# G4y_SuperCap.net
KiCad netlist of a schematic drawn in Altium Designer
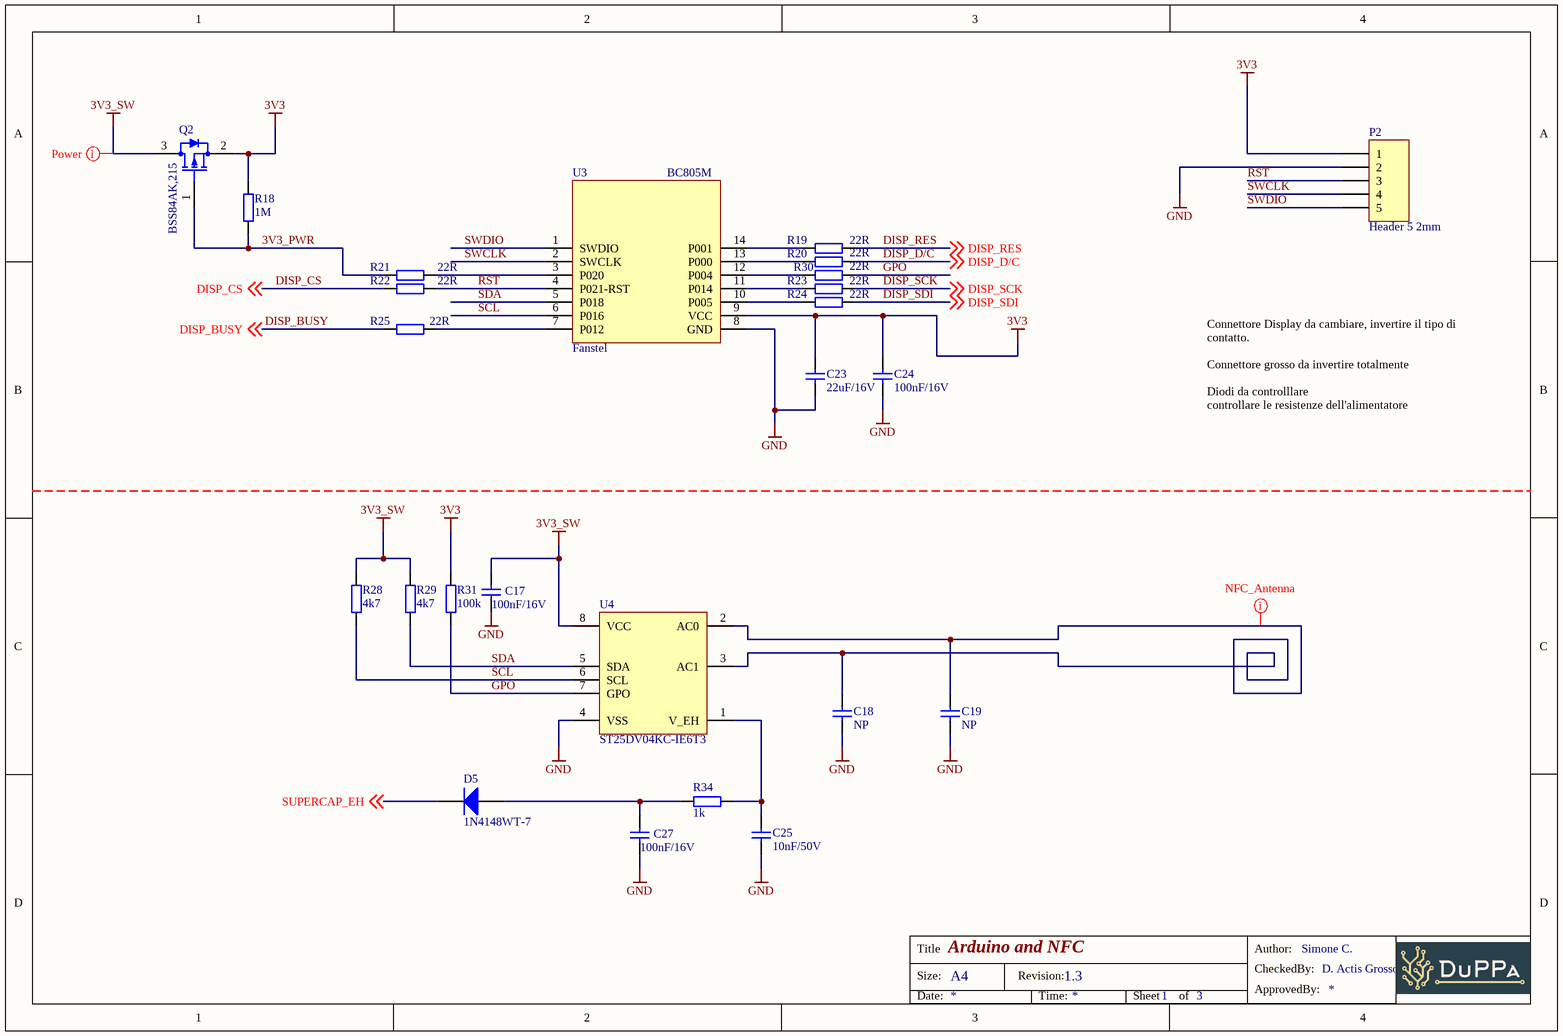
[diagram p0: G4y_SuperCap.SchDoc]

(export (version "E")
  (design (tool "Eeschema 10.0.6"))
  (components
    (comp (ref "C17")
      (value "100nF/16V")
      (footprint "C0402")
      (description "16V 100nF X7R ±10% 0402 Multilayer Ceramic Capacitors MLCC - SMD/SMT ROHS")
      (fields
        (field (name "PARTNUMBER") "CL05B104KO5NNNC")
        (field (name "MANUFACTURER") "Samsung Electro-Mechanics")
      )
      (libsource (lib "DuPPa_Lib") (part "Cap_0402_100n/16V"))
    )
    (comp (ref "C18")
      (value "NP")
      (footprint "C0402")
      (fields (field (name "Comment") "Cap_0402_NP"))
      (libsource (lib "DuPPa_Lib") (part "Cap_0402_NP"))
    )
    (comp (ref "C19")
      (value "NP")
      (footprint "C0402")
      (fields (field (name "Comment") "Cap_0402_NP"))
      (libsource (lib "DuPPa_Lib") (part "Cap_0402_NP"))
    )
    (comp (ref "C23")
      (value "22uF/16V")
      (footprint "C0805")
      (description "22uF ±20% 16V Ceramic Capacitor X5R 0805")
      (fields
        (field (name "PARTNUMBER") "CL21A226MOQNNNE")
        (field (name "MANUFACTURER") "Samsung Electro-Mechanics")
      )
      (libsource (lib "DuPPa_Lib") (part "Cap_0805_22uF/16V"))
    )
    (comp (ref "C24")
      (value "100nF/16V")
      (footprint "C0402")
      (description "16V 100nF X7R ±10% 0402 Multilayer Ceramic Capacitors MLCC - SMD/SMT ROHS")
      (fields
        (field (name "PARTNUMBER") "CL05B104KO5NNNC")
        (field (name "MANUFACTURER") "Samsung Electro-Mechanics")
      )
      (libsource (lib "DuPPa_Lib") (part "Cap_0402_100n/16V"))
    )
    (comp (ref "C25")
      (value "10nF/50V")
      (footprint "C0402")
      (description "10nF ±10% 50V Ceramic Capacitor X7R 0402")
      (fields
        (field (name "PARTNUMBER") "CL05B103KB5NNNC")
        (field (name "MANUFACTURER") "Samsung Electro-Mechanics")
      )
      (libsource (lib "DuPPa_Lib") (part "Cap_0402_10nF/50V"))
    )
    (comp (ref "C27")
      (value "100nF/16V")
      (footprint "C0402")
      (description "16V 100nF X7R ±10% 0402 Multilayer Ceramic Capacitors MLCC - SMD/SMT ROHS")
      (fields
        (field (name "PARTNUMBER") "CL05B104KO5NNNC")
        (field (name "MANUFACTURER") "Samsung Electro-Mechanics")
      )
      (libsource (lib "DuPPa_Lib") (part "Cap_0402_100n/16V"))
    )
    (comp (ref "D5")
      (value "Diode_1N4148WT")
      (footprint "SODFL160X65-2N")
      (description "Diode Independent 80V 125mA Surface Mount SOD-523")
      (fields (field (name "PARTNUMBER") "1N4148WT-7") (field (name "MANUFACTURER") "Diodes"))
      (libsource (lib "DuPPa_Lib") (part "Diode_1N4148WT"))
    )
    (comp (ref "P2")
      (value "Header 5 2mm")
      (footprint "HDR1X5_2mm")
      (description "Header, 5-Pin")
      (libsource (lib "DuPPa_Lib") (part "Header 5 2mm"))
    )
    (comp (ref "Q2")
      (value "BSS84AKBSS84AK,215")
      (footprint "SOT-23-3")
      (description "P-Channel 50V 180mA 420mW Surface Mount SOT-23")
      (fields (field (name "MANUFACTURER") "Nexperia") (field (name "PARTNUMBER") "BSS84AK,215"))
      (libsource (lib "DuPPa_Lib") (part "BSS84AKBSS84AK,215"))
    )
    (comp (ref "R18")
      (value "1M")
      (footprint "R0402")
      (description "1MΩ ±1% 62.5mW 0402 Thick Film Resistor")
      (fields (field (name "PARTNUMBER") "0402WGF1004TCE") (field (name "MANUFACTURER") "UNI-ROYAL"))
      (libsource (lib "DuPPa_Lib") (part "R_R0402_1M"))
    )
    (comp (ref "R19")
      (value "22R")
      (footprint "R0402")
      (description "22Ω ±1% 62.5mW 0402 Thick Film Resistor")
      (fields (field (name "PARTNUMBER") "0402WGF220JTCE") (field (name "MANUFACTURER") "UNI-ROYAL"))
      (libsource (lib "DuPPa_Lib") (part "R_R0402_22R"))
    )
    (comp (ref "R20")
      (value "22R")
      (footprint "R0402")
      (description "22Ω ±1% 62.5mW 0402 Thick Film Resistor")
      (fields (field (name "PARTNUMBER") "0402WGF220JTCE") (field (name "MANUFACTURER") "UNI-ROYAL"))
      (libsource (lib "DuPPa_Lib") (part "R_R0402_22R"))
    )
    (comp (ref "R21")
      (value "22R")
      (footprint "R0402")
      (description "22Ω ±1% 62.5mW 0402 Thick Film Resistor")
      (fields (field (name "PARTNUMBER") "0402WGF220JTCE") (field (name "MANUFACTURER") "UNI-ROYAL"))
      (libsource (lib "DuPPa_Lib") (part "R_R0402_22R"))
    )
    (comp (ref "R22")
      (value "22R")
      (footprint "R0402")
      (description "22Ω ±1% 62.5mW 0402 Thick Film Resistor")
      (fields (field (name "PARTNUMBER") "0402WGF220JTCE") (field (name "MANUFACTURER") "UNI-ROYAL"))
      (libsource (lib "DuPPa_Lib") (part "R_R0402_22R"))
    )
    (comp (ref "R23")
      (value "22R")
      (footprint "R0402")
      (description "22Ω ±1% 62.5mW 0402 Thick Film Resistor")
      (fields (field (name "PARTNUMBER") "0402WGF220JTCE") (field (name "MANUFACTURER") "UNI-ROYAL"))
      (libsource (lib "DuPPa_Lib") (part "R_R0402_22R"))
    )
    (comp (ref "R24")
      (value "22R")
      (footprint "R0402")
      (description "22Ω ±1% 62.5mW 0402 Thick Film Resistor")
      (fields (field (name "PARTNUMBER") "0402WGF220JTCE") (field (name "MANUFACTURER") "UNI-ROYAL"))
      (libsource (lib "DuPPa_Lib") (part "R_R0402_22R"))
    )
    (comp (ref "R25")
      (value "22R")
      (footprint "R0402")
      (description "22Ω ±1% 62.5mW 0402 Thick Film Resistor")
      (fields (field (name "PARTNUMBER") "0402WGF220JTCE") (field (name "MANUFACTURER") "UNI-ROYAL"))
      (libsource (lib "DuPPa_Lib") (part "R_R0402_22R"))
    )
    (comp (ref "R28")
      (value "4k7")
      (footprint "R0402")
      (description "0402, 1% ,63mW")
      (fields (field (name "PARTNUMBER") "0402WGF4701TCE") (field (name "Comment") "R_R0402_4k7"))
      (libsource (lib "DuPPa_Lib") (part "R_R0402_4k7"))
    )
    (comp (ref "R29")
      (value "4k7")
      (footprint "R0402")
      (description "0402, 1% ,63mW")
      (fields (field (name "PARTNUMBER") "0402WGF4701TCE") (field (name "Comment") "R_R0402_4k7"))
      (libsource (lib "DuPPa_Lib") (part "R_R0402_4k7"))
    )
    (comp (ref "R30")
      (value "22R")
      (footprint "R0402")
      (description "22Ω ±1% 62.5mW 0402 Thick Film Resistor")
      (fields (field (name "PARTNUMBER") "0402WGF220JTCE") (field (name "MANUFACTURER") "UNI-ROYAL"))
      (libsource (lib "DuPPa_Lib") (part "R_R0402_22R"))
    )
    (comp (ref "R31")
      (value "100k")
      (footprint "R0402")
      (description "0402, 1% ,63mW")
      (fields (field (name "PARTNUMBER") "ERA-2VEB1003X") (field (name "Comment") "R_R0402_100k"))
      (libsource (lib "DuPPa_Lib") (part "R_R0402_100k"))
    )
    (comp (ref "R34")
      (value "1k")
      (footprint "R0402")
      (description "0402, 1% ,63mW")
      (fields (field (name "PARTNUMBER") "0402WGJ0102TCE") (field (name "MANUFACTURER") "UNI-ROYAL"))
      (libsource (lib "DuPPa_Lib") (part "R_R0402_1k"))
    )
    (comp (ref "U3")
      (value "BLE Module")
      (footprint "BC805M")
      (fields (field (name "MANUFACTURER") "Fanstel") (field (name "PARTNUMBER") "BC805M"))
      (libsource (lib "DuPPa_Lib") (part "BC805M"))
    )
    (comp (ref "U4")
      (value "ST25DV04KC-IE6T3")
      (footprint "TSOP65P640X120-8N")
      (description "53Kbit/s ISO 15693,NFC I2C TSSOP-8 RFID, RF Access, Monitoring ICs RoHS")
      (fields
        (field (name "MANUFACTURER") "STMicroelectronics")
        (field (name "PARTNUMBER") "ST25DV04KC-IE6T3")
      )
      (libsource (lib "DuPPa_Lib") (part "ST25DV04KC-IE6T3"))
    )
  )
  (nets
    (net (code "1") (name "/3V3_PWR") (class "Default")
      (node (ref "Q2") (pin "1") (pinfunction "G_1") (pintype "passive"))
      (node (ref "R18") (pin "1") (pinfunction "1_1") (pintype "passive"))
      (node (ref "R21") (pin "1") (pinfunction "1_1") (pintype "passive"))
    )
    (net (code "2") (name "/GPO") (class "Default")
      (node (ref "R30") (pin "1") (pinfunction "1_1") (pintype "passive"))
      (node (ref "R31") (pin "1") (pinfunction "1_1") (pintype "passive"))
      (node (ref "U4") (pin "7") (pinfunction "GPO_7") (pintype "passive"))
    )
    (net (code "3") (name "/RST") (class "Default")
      (node (ref "P2") (pin "3") (pinfunction "3_3") (pintype "passive"))
      (node (ref "R22") (pin "2") (pinfunction "2_2") (pintype "passive"))
      (node (ref "U3") (pin "4") (pinfunction "P021-RST_4") (pintype "passive"))
    )
    (net (code "4") (name "/SCL") (class "Default")
      (node (ref "R28") (pin "2") (pinfunction "2_2") (pintype "passive"))
      (node (ref "U3") (pin "6") (pinfunction "P016_6") (pintype "passive"))
      (node (ref "U4") (pin "6") (pinfunction "SCL_6") (pintype "passive"))
    )
    (net (code "5") (name "/SDA") (class "Default")
      (node (ref "R29") (pin "2") (pinfunction "2_2") (pintype "passive"))
      (node (ref "U3") (pin "5") (pinfunction "P018_5") (pintype "passive"))
      (node (ref "U4") (pin "5") (pinfunction "SDA_5") (pintype "passive"))
    )
    (net (code "6") (name "/SWCLK") (class "Default")
      (node (ref "P2") (pin "4") (pinfunction "4_4") (pintype "passive"))
      (node (ref "U3") (pin "2") (pinfunction "SWCLK_2") (pintype "passive"))
    )
    (net (code "7") (name "/SWDIO") (class "Default")
      (node (ref "P2") (pin "5") (pinfunction "5_5") (pintype "passive"))
      (node (ref "U3") (pin "1") (pinfunction "SWDIO_1") (pintype "passive"))
    )
    (net (code "8") (name "3V3") (class "Default")
      (node (ref "C23") (pin "1") (pinfunction "1_1") (pintype "passive"))
      (node (ref "C24") (pin "1") (pinfunction "1_1") (pintype "passive"))
      (node (ref "P2") (pin "1") (pinfunction "1_1") (pintype "passive"))
      (node (ref "Q2") (pin "2") (pinfunction "S_2") (pintype "passive"))
      (node (ref "R18") (pin "2") (pinfunction "2_2") (pintype "passive"))
      (node (ref "R31") (pin "2") (pinfunction "2_2") (pintype "passive"))
      (node (ref "U3") (pin "9") (pinfunction "VCC_9") (pintype "passive"))
    )
    (net (code "9") (name "3V3_SW") (class "Default")
      (node (ref "C17") (pin "1") (pinfunction "1_1") (pintype "passive"))
      (node (ref "Q2") (pin "3") (pinfunction "D_3") (pintype "passive"))
      (node (ref "R28") (pin "1") (pinfunction "1_1") (pintype "passive"))
      (node (ref "R29") (pin "1") (pinfunction "1_1") (pintype "passive"))
      (node (ref "U4") (pin "8") (pinfunction "VCC_8") (pintype "passive"))
    )
    (net (code "10") (name "DISP_BUSY") (class "Default")
      (node (ref "R25") (pin "1") (pinfunction "1_1") (pintype "passive"))
    )
    (net (code "11") (name "DISP_CS") (class "Default")
      (node (ref "R22") (pin "1") (pinfunction "1_1") (pintype "passive"))
    )
    (net (code "12") (name "DISP_D{slash}C") (class "Default")
      (node (ref "R20") (pin "1") (pinfunction "1_1") (pintype "passive"))
    )
    (net (code "13") (name "DISP_RES") (class "Default")
      (node (ref "R19") (pin "1") (pinfunction "1_1") (pintype "passive"))
    )
    (net (code "14") (name "DISP_SCK") (class "Default")
      (node (ref "R23") (pin "1") (pinfunction "1_1") (pintype "passive"))
    )
    (net (code "15") (name "DISP_SDI") (class "Default")
      (node (ref "R24") (pin "1") (pinfunction "1_1") (pintype "passive"))
    )
    (net (code "16") (name "GND") (class "Default")
      (node (ref "C17") (pin "2") (pinfunction "2_2") (pintype "passive"))
      (node (ref "C18") (pin "2") (pinfunction "2_2") (pintype "passive"))
      (node (ref "C19") (pin "2") (pinfunction "2_2") (pintype "passive"))
      (node (ref "C23") (pin "2") (pinfunction "2_2") (pintype "passive"))
      (node (ref "C24") (pin "2") (pinfunction "2_2") (pintype "passive"))
      (node (ref "C25") (pin "2") (pinfunction "2_2") (pintype "passive"))
      (node (ref "C27") (pin "2") (pinfunction "2_2") (pintype "passive"))
      (node (ref "P2") (pin "2") (pinfunction "2_2") (pintype "passive"))
      (node (ref "U3") (pin "8") (pinfunction "GND_8") (pintype "passive"))
      (node (ref "U4") (pin "4") (pinfunction "VSS_4") (pintype "passive"))
    )
    (net (code "17") (name "Net-(C27-Pad1)") (class "Default")
      (node (ref "C27") (pin "1") (pinfunction "1_1") (pintype "passive"))
      (node (ref "D5") (pin "A") (pinfunction "A_A") (pintype "passive"))
      (node (ref "R34") (pin "1") (pinfunction "1_1") (pintype "passive"))
    )
    (net (code "18") (name "Net-(U3-P000)") (class "Default")
      (node (ref "R20") (pin "2") (pinfunction "2_2") (pintype "passive"))
      (node (ref "U3") (pin "13") (pinfunction "P000_13") (pintype "passive"))
    )
    (net (code "19") (name "Net-(U3-P001)") (class "Default")
      (node (ref "R19") (pin "2") (pinfunction "2_2") (pintype "passive"))
      (node (ref "U3") (pin "14") (pinfunction "P001_14") (pintype "passive"))
    )
    (net (code "20") (name "Net-(U3-P004)") (class "Default")
      (node (ref "R30") (pin "2") (pinfunction "2_2") (pintype "passive"))
      (node (ref "U3") (pin "12") (pinfunction "P004_12") (pintype "passive"))
    )
    (net (code "21") (name "Net-(U3-P005)") (class "Default")
      (node (ref "R24") (pin "2") (pinfunction "2_2") (pintype "passive"))
      (node (ref "U3") (pin "10") (pinfunction "P005_10") (pintype "passive"))
    )
    (net (code "22") (name "Net-(U3-P012)") (class "Default")
      (node (ref "R25") (pin "2") (pinfunction "2_2") (pintype "passive"))
      (node (ref "U3") (pin "7") (pinfunction "P012_7") (pintype "passive"))
    )
    (net (code "23") (name "Net-(U3-P014)") (class "Default")
      (node (ref "R23") (pin "2") (pinfunction "2_2") (pintype "passive"))
      (node (ref "U3") (pin "11") (pinfunction "P014_11") (pintype "passive"))
    )
    (net (code "24") (name "Net-(U3-P020)") (class "Default")
      (node (ref "R21") (pin "2") (pinfunction "2_2") (pintype "passive"))
      (node (ref "U3") (pin "3") (pinfunction "P020_3") (pintype "passive"))
    )
    (net (code "25") (name "Net-(U4-AC0)") (class "Default")
      (node (ref "C18") (pin "1") (pinfunction "1_1") (pintype "passive"))
      (node (ref "C19") (pin "1") (pinfunction "1_1") (pintype "passive"))
      (node (ref "U4") (pin "2") (pinfunction "AC0_2") (pintype "passive"))
      (node (ref "U4") (pin "3") (pinfunction "AC1_3") (pintype "passive"))
    )
    (net (code "26") (name "Net-(U4-V_EH)") (class "Default")
      (node (ref "C25") (pin "1") (pinfunction "1_1") (pintype "passive"))
      (node (ref "R34") (pin "2") (pinfunction "2_2") (pintype "passive"))
      (node (ref "U4") (pin "1") (pinfunction "V_EH_1") (pintype "passive"))
    )
    (net (code "27") (name "SUPERCAP_EH") (class "Default")
      (node (ref "D5") (pin "K") (pinfunction "K_K") (pintype "passive"))
    )
  )
)
